# Signal_Latch_Logic.net
KiCad netlist of a schematic drawn in Altium Designer
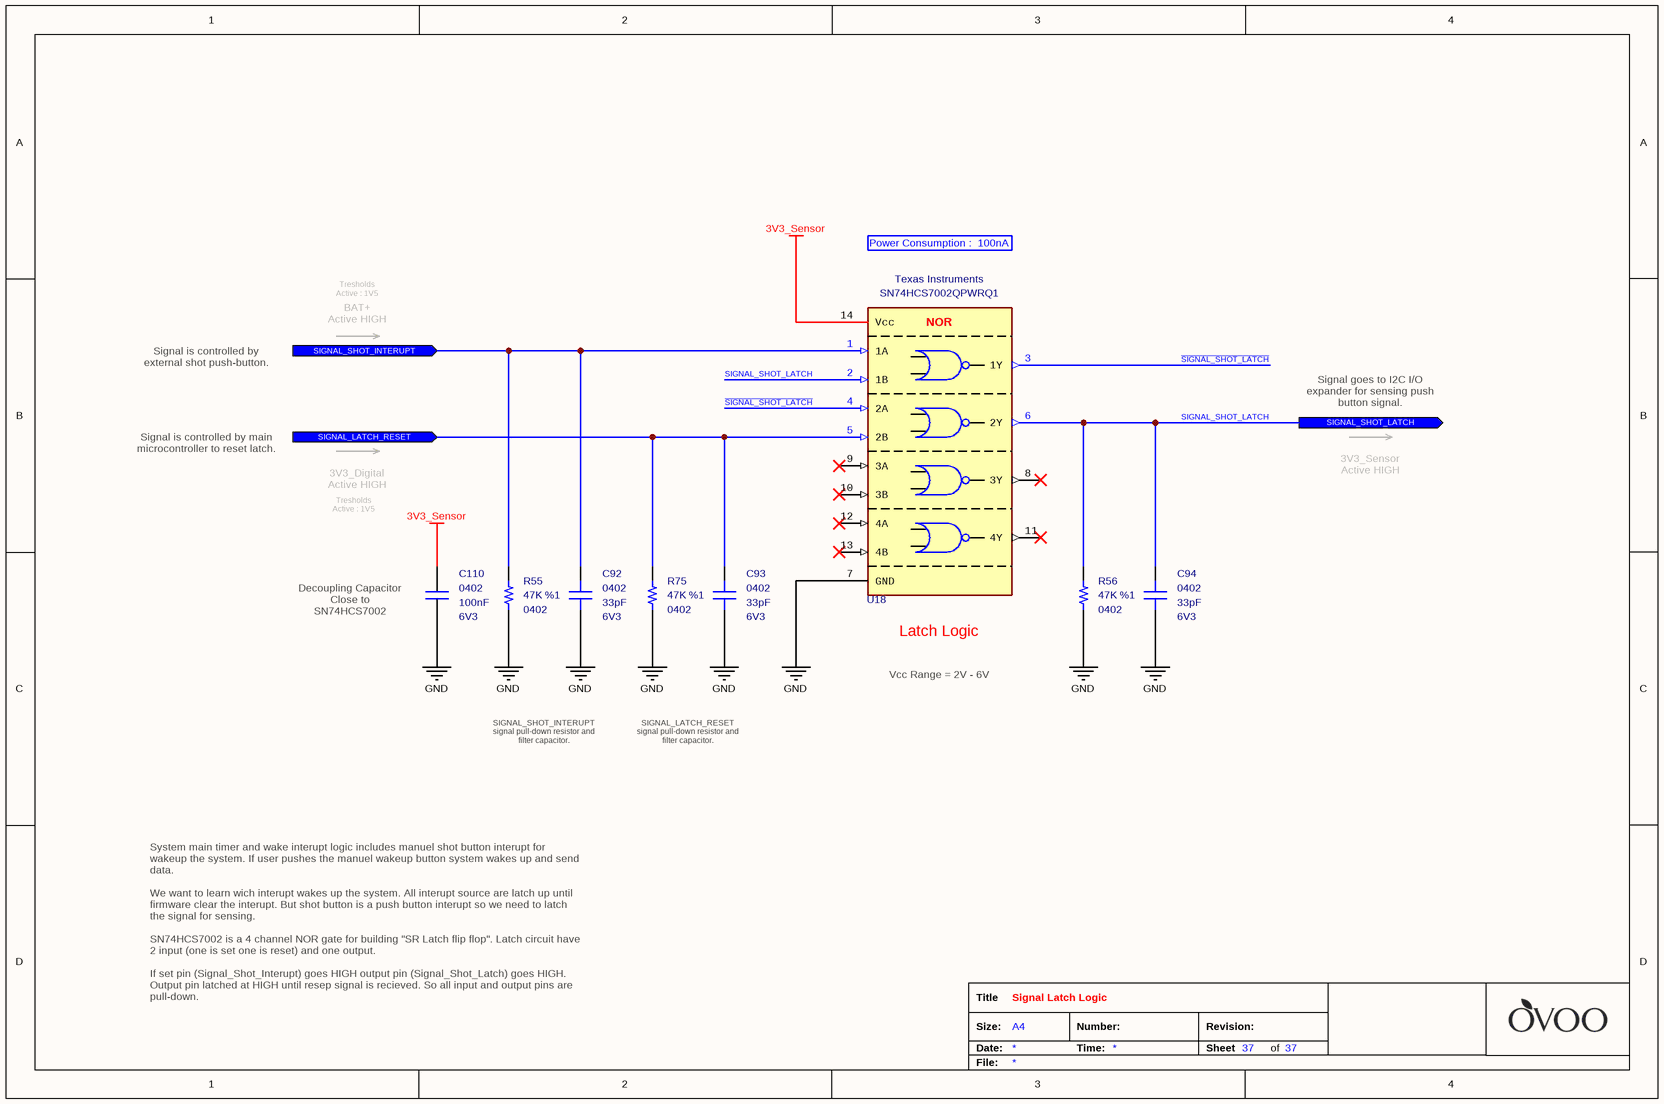
[diagram p0: Signal Latch Logic.SchDoc]

(export (version "E")
  (design (tool "Eeschema 10.0.6"))
  (components
    (comp (ref "C92")
      (value "33pF")
      (footprint "CAPACITOR_0402")
      (description "Capacitor - 33pF [0402] (Ceramic)")
      (fields
        (field (name "MANUFACTURER_PART_NUMBER") "C0402C330J9RACAUTO")
        (field (name "MOUSER_PART_NUMBER") "80-C0402C330J9RAUTO")
        (field (name "CASE") "0402")
        (field (name "VOLTAGE") "6V3")
      )
      (libsource (lib "Ovoo_Schematic") (part "Capacitor - 33pF [0402-6V3]"))
    )
    (comp (ref "C93")
      (value "33pF")
      (footprint "CAPACITOR_0402")
      (description "Capacitor - 33pF [0402] (Ceramic)")
      (fields
        (field (name "MANUFACTURER_PART_NUMBER") "C0402C330J9RACAUTO")
        (field (name "MOUSER_PART_NUMBER") "80-C0402C330J9RAUTO")
        (field (name "CASE") "0402")
        (field (name "VOLTAGE") "6V3")
      )
      (libsource (lib "Ovoo_Schematic") (part "Capacitor - 33pF [0402-6V3]"))
    )
    (comp (ref "C94")
      (value "33pF")
      (footprint "CAPACITOR_0402")
      (description "Capacitor - 33pF [0402] (Ceramic)")
      (fields
        (field (name "MANUFACTURER_PART_NUMBER") "C0402C330J9RACAUTO")
        (field (name "MOUSER_PART_NUMBER") "80-C0402C330J9RAUTO")
        (field (name "CASE") "0402")
        (field (name "VOLTAGE") "6V3")
      )
      (libsource (lib "Ovoo_Schematic") (part "Capacitor - 33pF [0402-6V3]"))
    )
    (comp (ref "C110")
      (value "100nF")
      (footprint "CAPACITOR_0402")
      (description "Capacitor - 100nF [0402-6V3] (Ceramic)")
      (fields
        (field (name "MANUFACTURER_PART_NUMBER") "04026D104KAT4A")
        (field (name "MOUSER_PART_NUMBER") "581-04026D104KAT4A")
        (field (name "CASE") "0402")
        (field (name "VOLTAGE") "6V3")
      )
      (libsource (lib "Ovoo_Schematic") (part "Capacitor - 100nF [0402-6V3]"))
    )
    (comp (ref "R55")
      (value "47K")
      (footprint "RESISTOR_0402")
      (description "Thick Film Resistors - SMD 1/16 W 47 Kohms 1%")
      (fields
        (field (name "MANUFACTURER_PART_NUMBER") "CRCW040247K0FKED")
        (field (name "MOUSER_PART_NUMBER") "71-CRCW0402-47K-E3")
        (field (name "TOLERANCE") "%1")
        (field (name "CASE") "0402")
      )
      (libsource (lib "Ovoo_Schematic") (part "Resistor - 47K"))
    )
    (comp (ref "R56")
      (value "47K")
      (footprint "RESISTOR_0402")
      (description "Thick Film Resistors - SMD 1/16 W 47 Kohms 1%")
      (fields
        (field (name "MANUFACTURER_PART_NUMBER") "CRCW040247K0FKED")
        (field (name "MOUSER_PART_NUMBER") "71-CRCW0402-47K-E3")
        (field (name "TOLERANCE") "%1")
        (field (name "CASE") "0402")
      )
      (libsource (lib "Ovoo_Schematic") (part "Resistor - 47K"))
    )
    (comp (ref "R75")
      (value "47K")
      (footprint "RESISTOR_0402")
      (description "Thick Film Resistors - SMD 1/16 W 47 Kohms 1%")
      (fields
        (field (name "MANUFACTURER_PART_NUMBER") "CRCW040247K0FKED")
        (field (name "MOUSER_PART_NUMBER") "71-CRCW0402-47K-E3")
        (field (name "TOLERANCE") "%1")
        (field (name "CASE") "0402")
      )
      (libsource (lib "Ovoo_Schematic") (part "Resistor - 47K"))
    )
    (comp (ref "U18")
      (value "Logic Gate (NOR)")
      (footprint "TSSOP-14")
      (description "Logic Gates Quadruple 2-input NOR gates with Schmitt-trigger inputs 14-TSSOP -40 to 125")
      (fields
        (field (name "MOUSER_PART_NUMBER") "595-N74HCS7002QPWRQ1")
        (field (name "MANUFACTURER_PART_NUMBER") "SN74HCS7002QPWRQ1")
        (field (name "MANUFACTURER_NAME") "Texas Instruments")
      )
      (libsource (lib "Ovoo_Schematic") (part "IC - SN74HCS7002QPWRQ1"))
    )
  )
  (nets
    (net (code "1") (name "/SIGNAL_LATCH_RESET") (class "Default")
      (node (ref "C93") (pin "2") (pinfunction "2_2") (pintype "passive"))
      (node (ref "R75") (pin "2") (pinfunction "2_2") (pintype "passive"))
      (node (ref "U18") (pin "5") (pinfunction "2B_5") (pintype "input"))
    )
    (net (code "2") (name "/SIGNAL_SHOT_INTERUPT") (class "Default")
      (node (ref "C92") (pin "2") (pinfunction "2_2") (pintype "passive"))
      (node (ref "R55") (pin "2") (pinfunction "2_2") (pintype "passive"))
      (node (ref "U18") (pin "1") (pinfunction "1A_1") (pintype "input"))
    )
    (net (code "3") (name "/SIGNAL_SHOT_LATCH") (class "Default")
      (node (ref "C94") (pin "2") (pinfunction "2_2") (pintype "passive"))
      (node (ref "R56") (pin "2") (pinfunction "2_2") (pintype "passive"))
      (node (ref "U18") (pin "2") (pinfunction "1B_2") (pintype "input"))
      (node (ref "U18") (pin "6") (pinfunction "2Y_6") (pintype "output"))
    )
    (net (code "4") (name "/~{SIGNAL_SHOT_LATCH}") (class "Default")
      (node (ref "U18") (pin "3") (pinfunction "1Y_3") (pintype "output"))
      (node (ref "U18") (pin "4") (pinfunction "2A_4") (pintype "input"))
    )
    (net (code "5") (name "3V3_Sensor") (class "Default")
      (node (ref "C110") (pin "2") (pinfunction "2_2") (pintype "passive"))
      (node (ref "U18") (pin "14") (pinfunction "Vcc_14") (pintype "power_in"))
    )
    (net (code "6") (name "GND") (class "Default")
      (node (ref "C110") (pin "1") (pinfunction "1_1") (pintype "passive"))
      (node (ref "C92") (pin "1") (pinfunction "1_1") (pintype "passive"))
      (node (ref "C93") (pin "1") (pinfunction "1_1") (pintype "passive"))
      (node (ref "C94") (pin "1") (pinfunction "1_1") (pintype "passive"))
      (node (ref "R55") (pin "1") (pinfunction "1_1") (pintype "passive"))
      (node (ref "R56") (pin "1") (pinfunction "1_1") (pintype "passive"))
      (node (ref "R75") (pin "1") (pinfunction "1_1") (pintype "passive"))
      (node (ref "U18") (pin "7") (pinfunction "GND_7") (pintype "power_in"))
    )
    (net (code "7") (name "unconnected-(U18-3A-Pad9)") (class "Default")
      (node (ref "U18") (pin "9") (pinfunction "3A_9") (pintype "input+no_connect"))
    )
    (net (code "8") (name "unconnected-(U18-3B-Pad10)") (class "Default")
      (node (ref "U18") (pin "10") (pinfunction "3B_10") (pintype "input+no_connect"))
    )
    (net (code "9") (name "unconnected-(U18-3Y-Pad8)") (class "Default")
      (node (ref "U18") (pin "8") (pinfunction "3Y_8") (pintype "output+no_connect"))
    )
    (net (code "10") (name "unconnected-(U18-4A-Pad12)") (class "Default")
      (node (ref "U18") (pin "12") (pinfunction "4A_12") (pintype "input+no_connect"))
    )
    (net (code "11") (name "unconnected-(U18-4B-Pad13)") (class "Default")
      (node (ref "U18") (pin "13") (pinfunction "4B_13") (pintype "input+no_connect"))
    )
    (net (code "12") (name "unconnected-(U18-4Y-Pad11)") (class "Default")
      (node (ref "U18") (pin "11") (pinfunction "4Y_11") (pintype "output+no_connect"))
    )
  )
)
